# LcsNodes-Extension-GPIO-Board-32-S-B_00_.net
KiCad netlist of a schematic drawn in EasyEDA
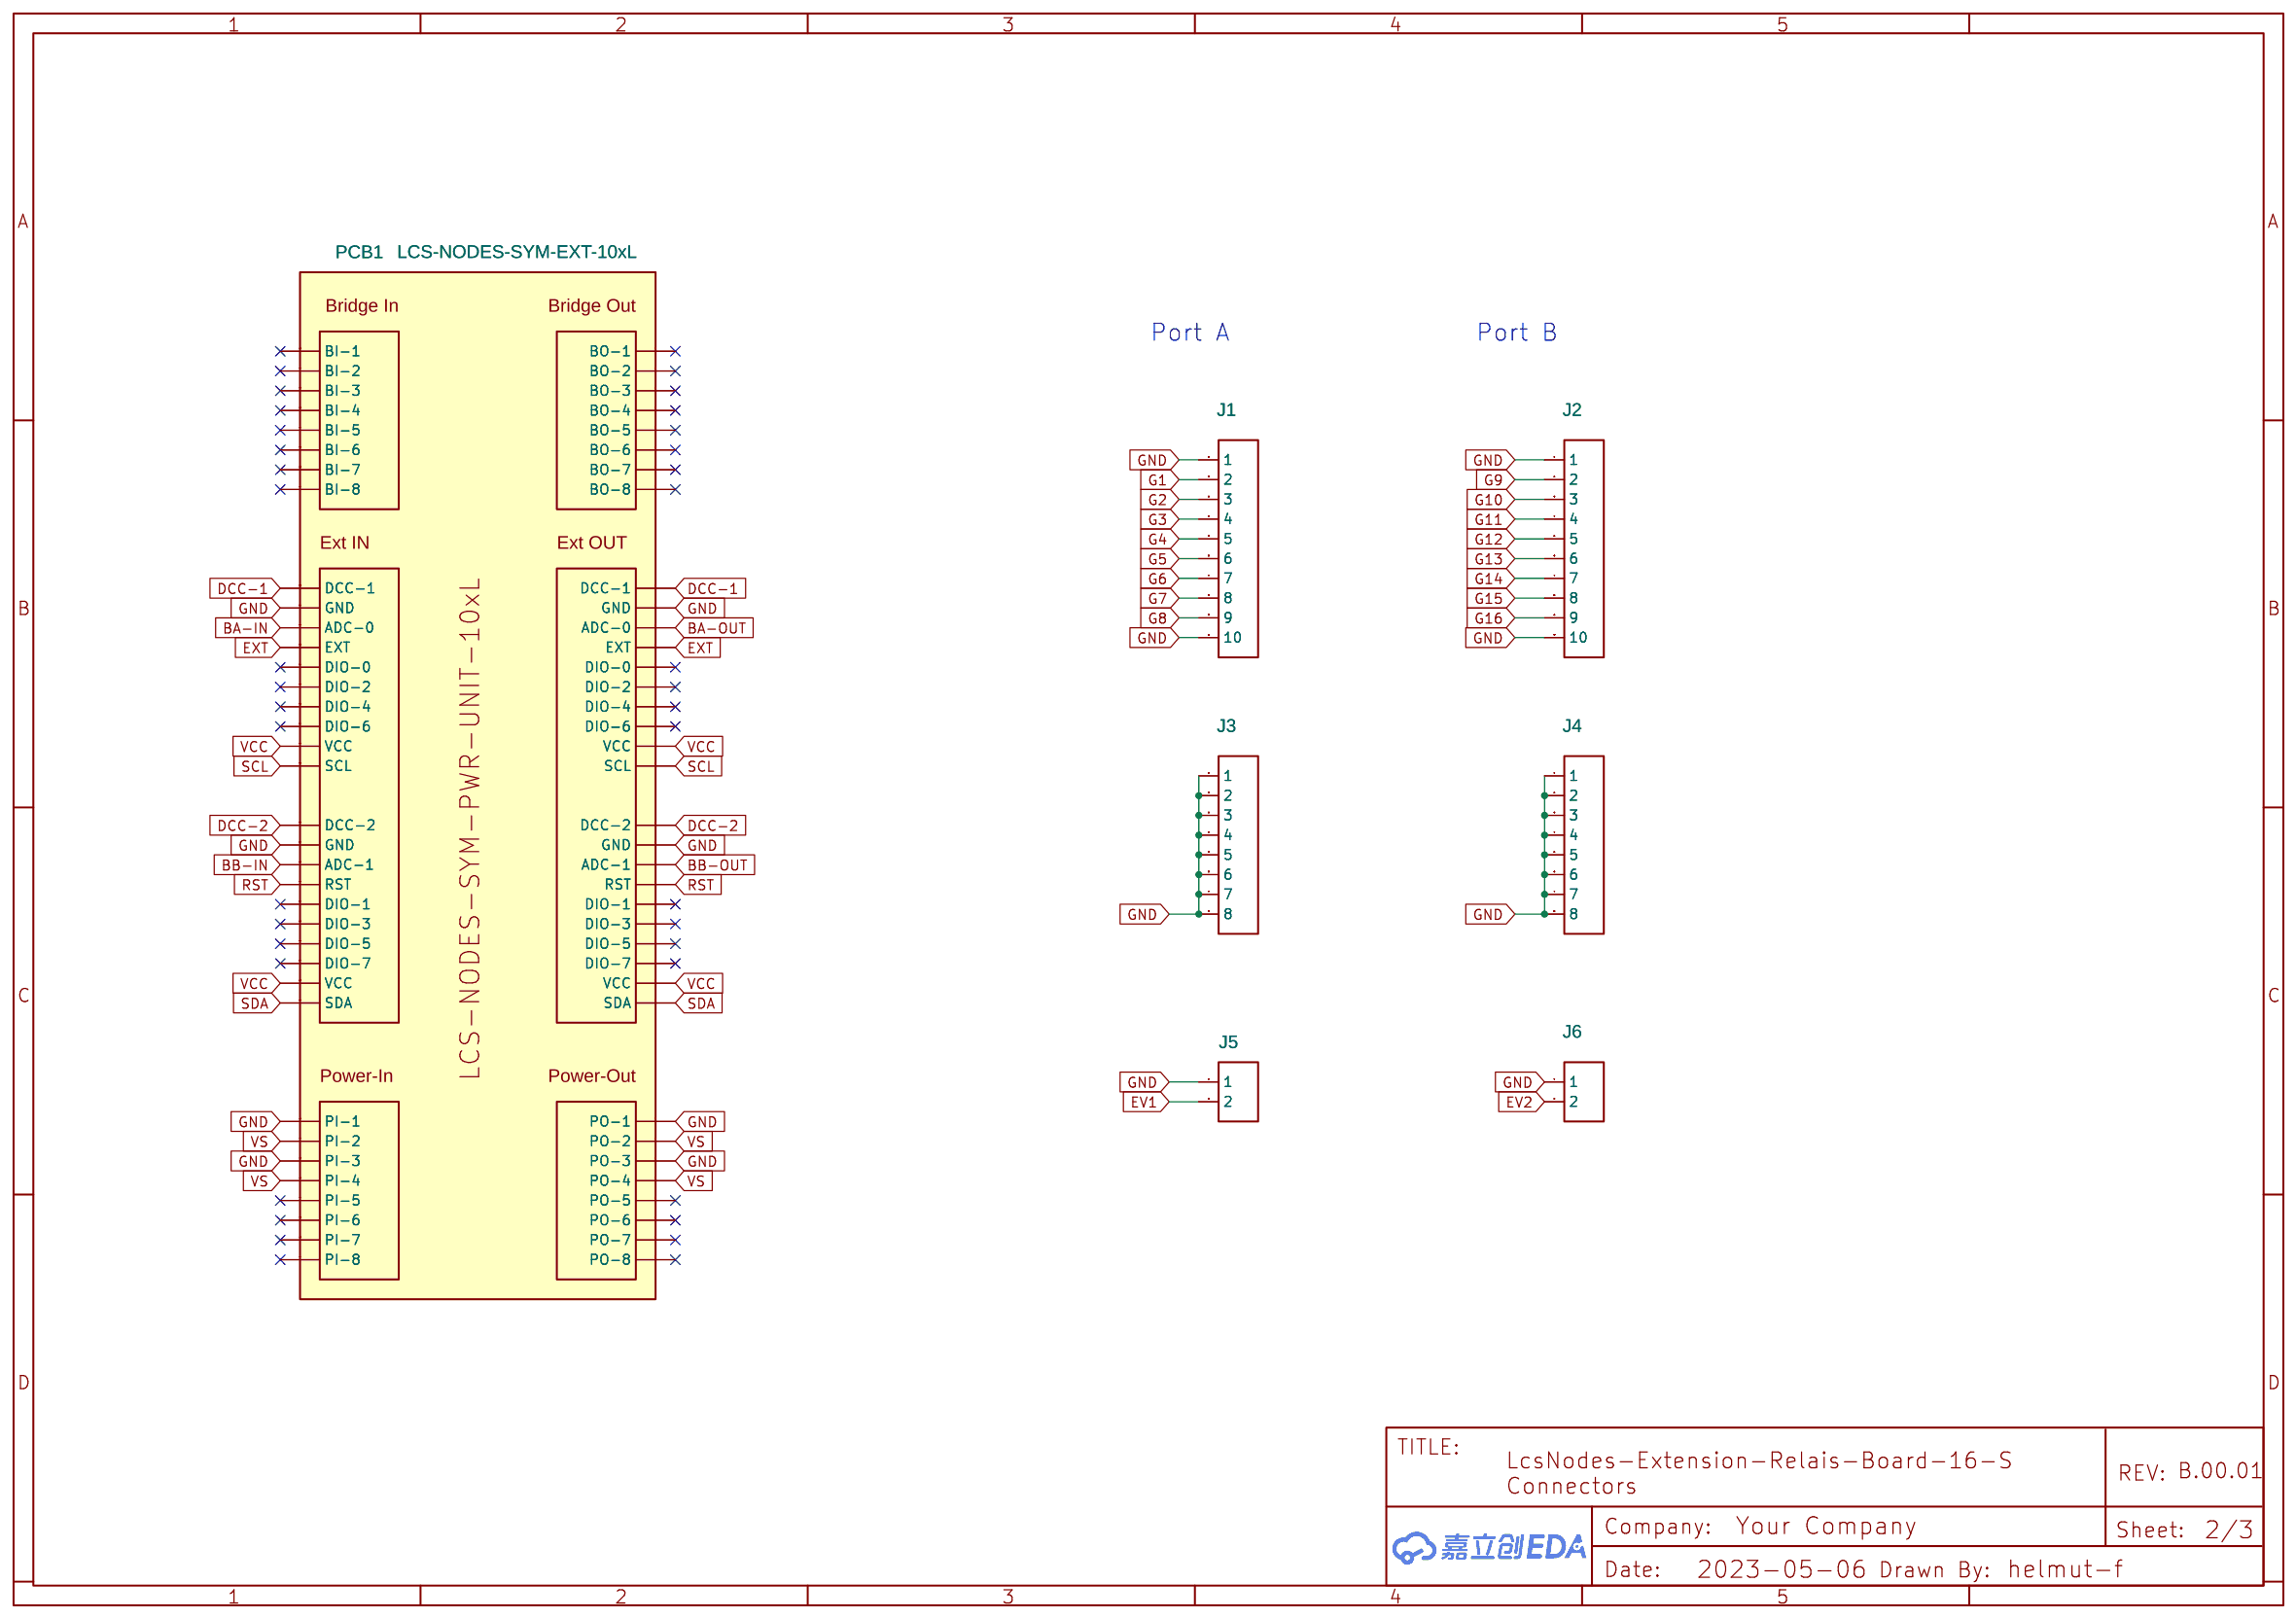
[diagram p0: Connectors]
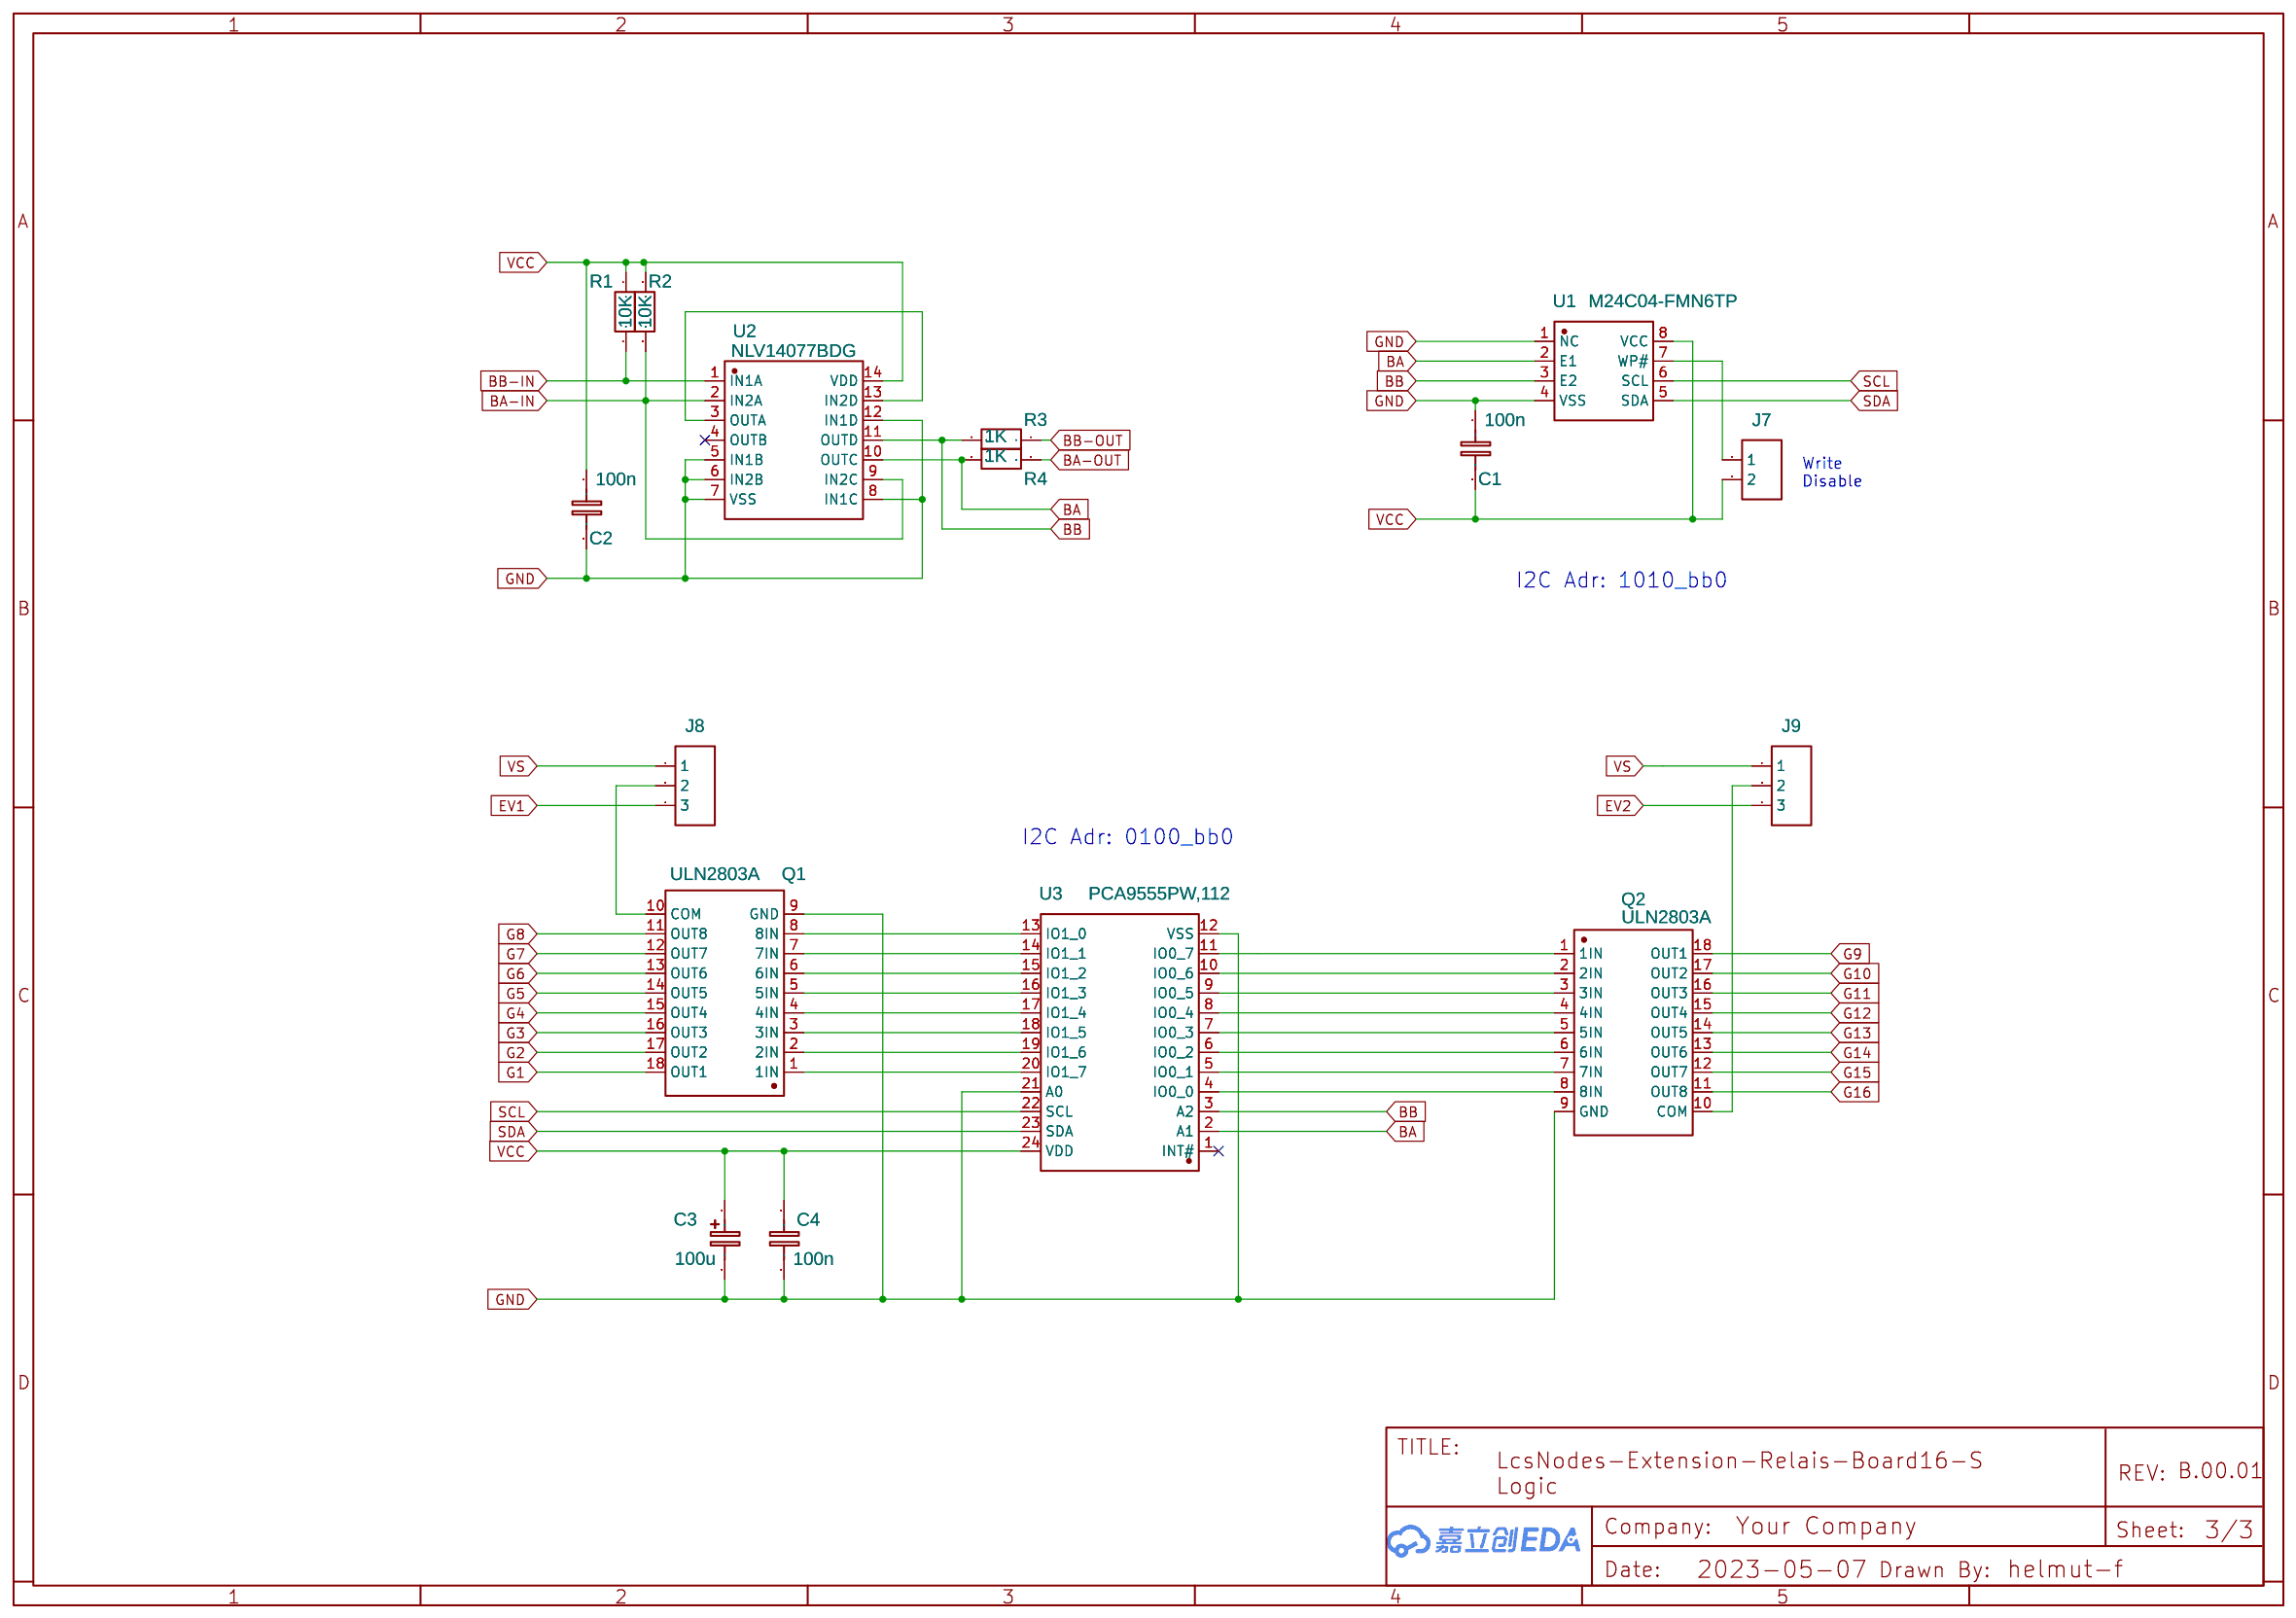
[diagram p1: Logic]
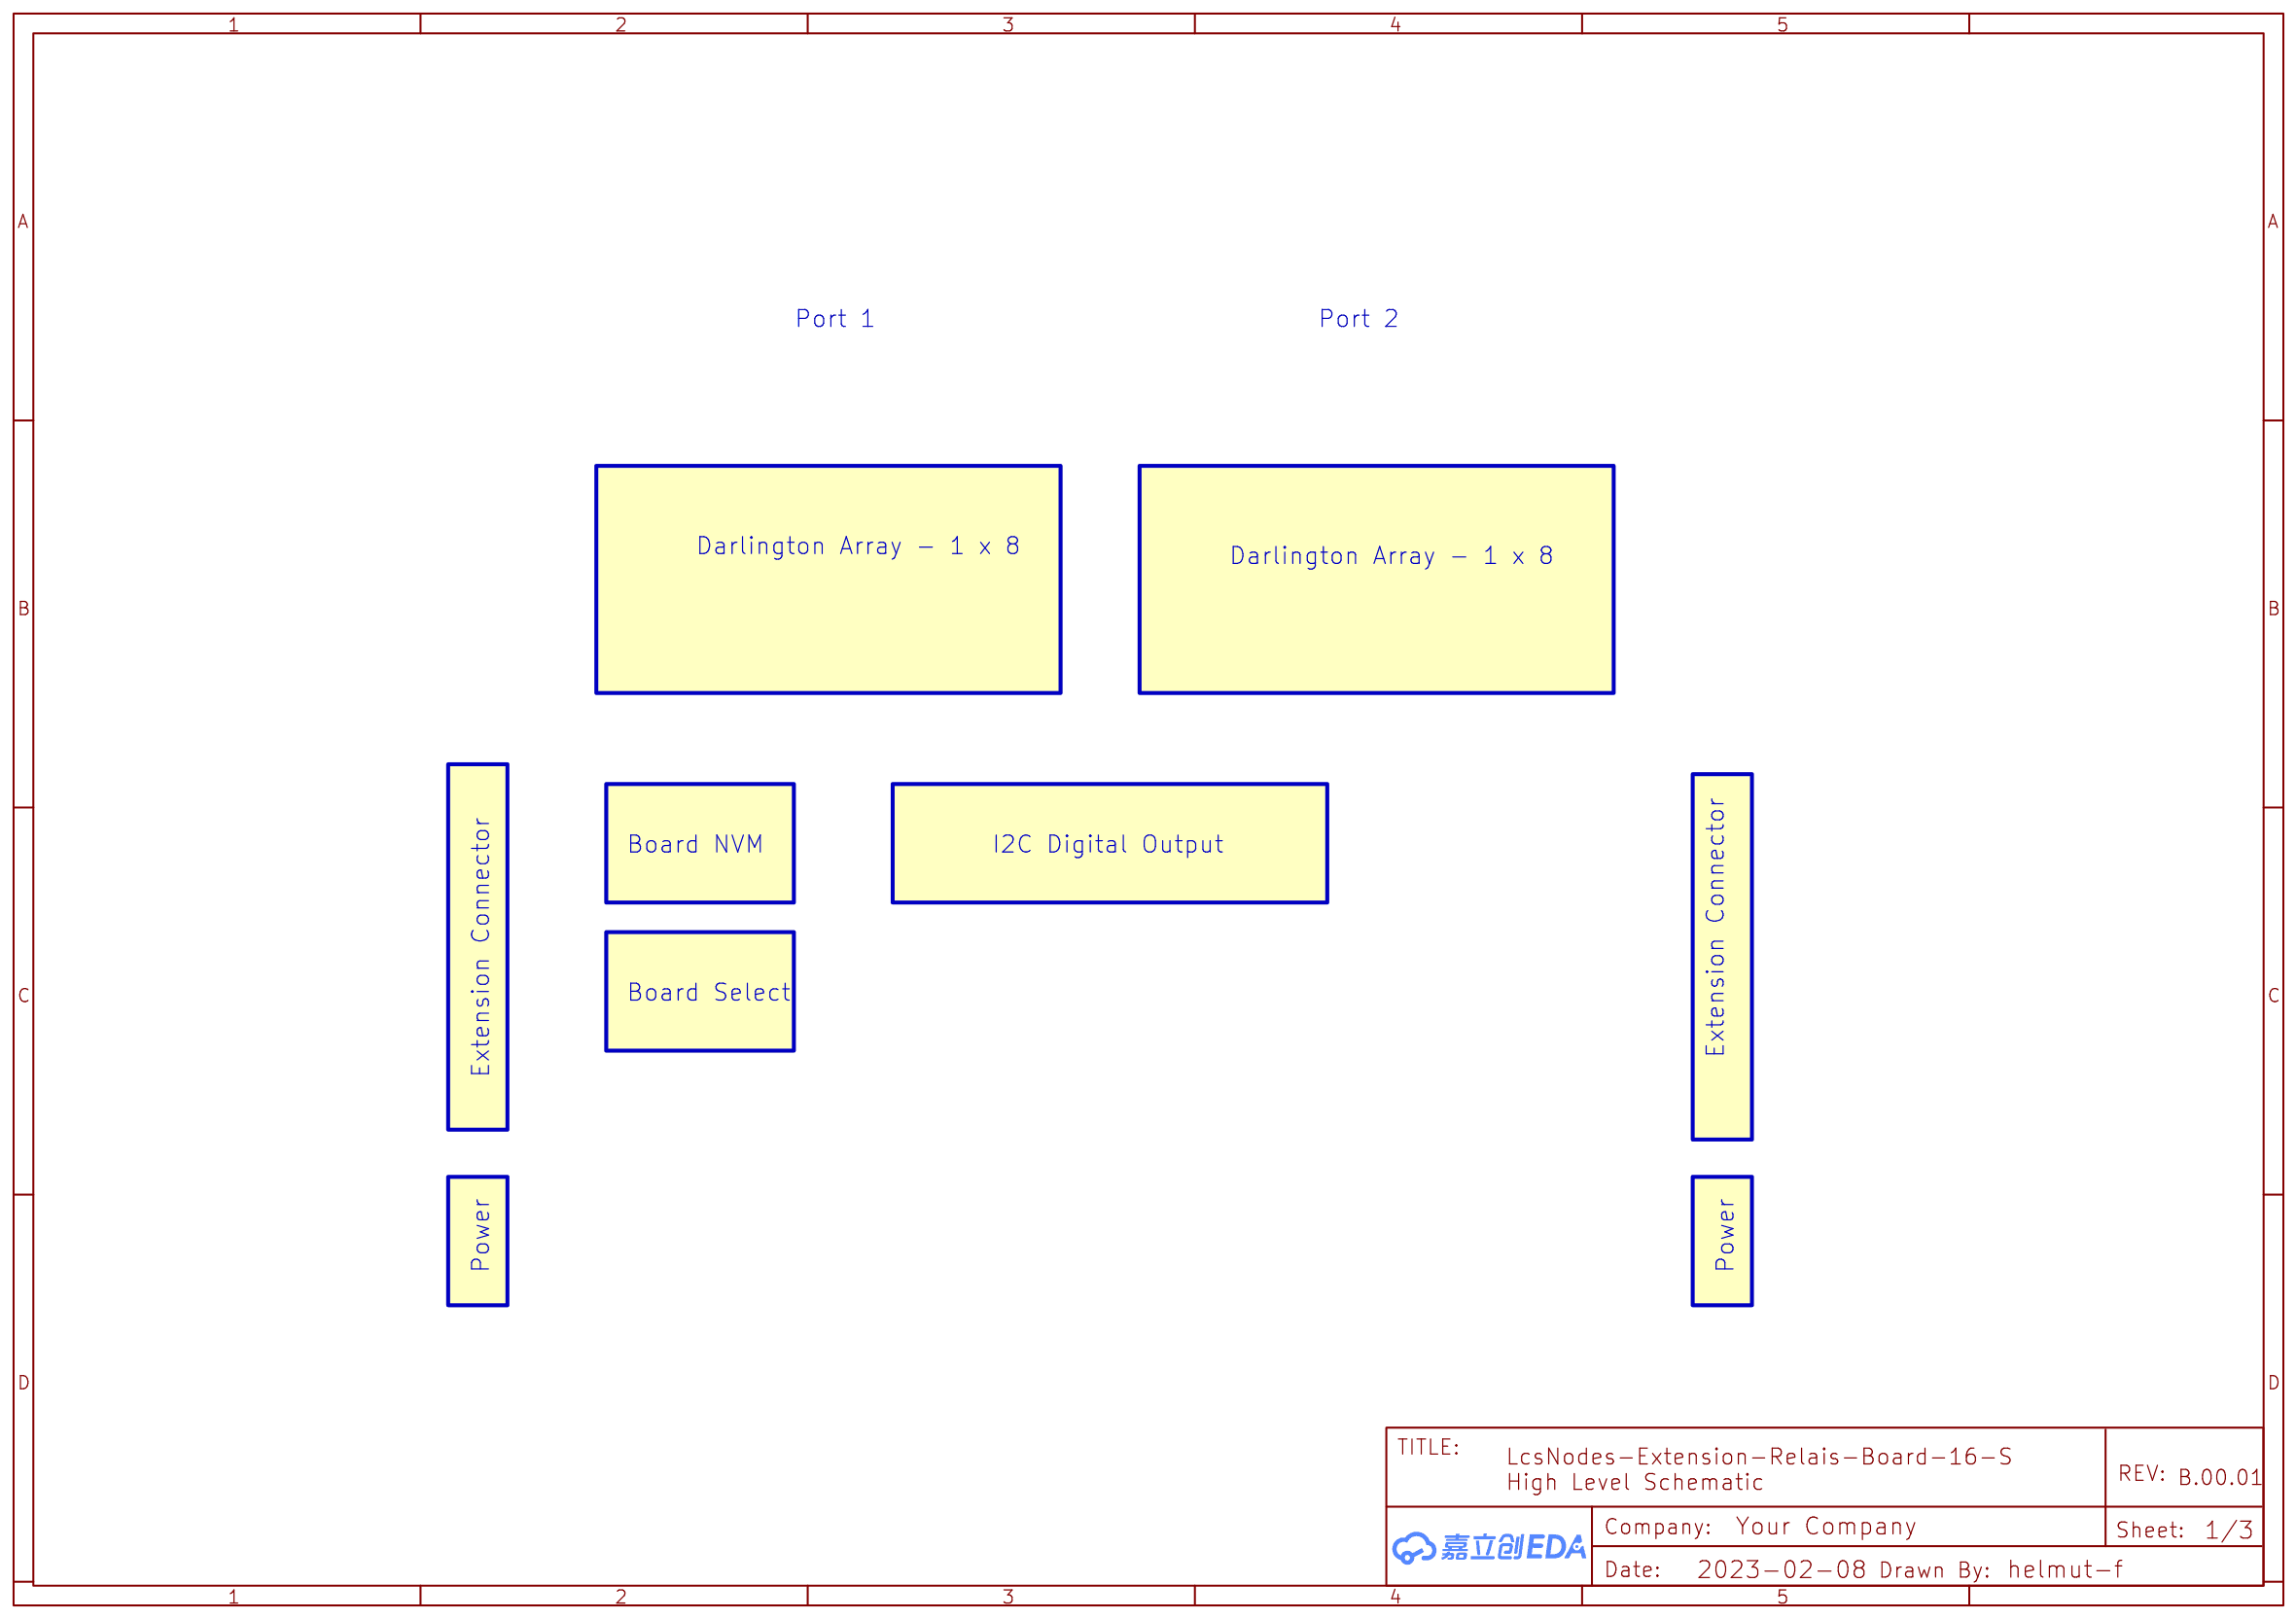
[diagram p2: High Level Schematic]

(export (version "E")
  (design (tool "Eeschema 10.0.6"))
  (components
    (comp (ref "J1") (value "HDR-M-2.54_1x10") (libsource (lib "") (part "HDR-M-2.54_1x10")))
    (comp (ref "J2") (value "HDR-M-2.54_1x10") (libsource (lib "") (part "HDR-M-2.54_1x10")))
    (comp (ref "J3") (value "HDR-M-2.54_1x8") (libsource (lib "") (part "HDR-M-2.54_1x8")))
    (comp (ref "J4") (value "HDR-M-2.54_1x8") (libsource (lib "") (part "HDR-M-2.54_1x8")))
    (comp (ref "J5") (value "HDR-M-2.54_1x2") (libsource (lib "") (part "HDR-M-2.54_1x2")))
    (comp (ref "J6") (value "HDR-M-2.54_1x2") (libsource (lib "") (part "HDR-M-2.54_1x2")))
    (comp (ref "PCB1") (value "LCS-NODES-SYM-EXT-10xL") (libsource (lib "") (part "LCS-NODES-SYM-EXT-10xL")))
    (comp (ref "C1") (value "100n") (libsource (lib "") (part "C_0603_EU_2")))
    (comp (ref "C2") (value "100n") (libsource (lib "") (part "C_0603_EU_1")))
    (comp (ref "C3") (value "100u") (libsource (lib "") (part "CE_TH_D4.0×F1.5_EU")))
    (comp (ref "C4") (value "100n") (libsource (lib "") (part "C_0603_EU")))
    (comp (ref "J7") (value "HDR-M-2.54_1x2") (libsource (lib "") (part "HDR-M-2.54_1x2")))
    (comp (ref "J8") (value "HDR-M-2.54_1x3") (libsource (lib "") (part "HDR-M-2.54_1x3")))
    (comp (ref "J9") (value "HDR-M-2.54_1x3") (libsource (lib "") (part "HDR-M-2.54_1x3")))
    (comp (ref "Q1")
      (value "ULN2803A")
      (fields (field (name "Manufacturer") "STMicroelectronics"))
      (libsource (lib "") (part "ULN2803A_1"))
    )
    (comp (ref "Q2")
      (value "ULN2803A")
      (fields (field (name "Manufacturer") "STMicroelectronics"))
      (libsource (lib "") (part "ULN2803A"))
    )
    (comp (ref "R1") (value "10K") (libsource (lib "") (part "R_AXIAL-0.3_EU_1")))
    (comp (ref "R2") (value "10K") (libsource (lib "") (part "R_AXIAL-0.3_EU_1")))
    (comp (ref "R3") (value "1K") (libsource (lib "") (part "R_AXIAL-0.3_EU")))
    (comp (ref "R4") (value "1K") (libsource (lib "") (part "R_AXIAL-0.3_EU")))
    (comp (ref "U1")
      (value "M24C04-FMN6TP")
      (fields (field (name "Manufacturer") "ST(意法半导体)"))
      (libsource (lib "") (part "M24C04-FMN6TP"))
    )
    (comp (ref "U2")
      (value "NLV14077BDG")
      (fields (field (name "Manufacturer") "onsemi(安森美)"))
      (libsource (lib "") (part "NLV14077BDG"))
    )
    (comp (ref "U3")
      (value "PCA9555PW,112")
      (fields (field (name "Manufacturer") "NXP(恩智浦)"))
      (libsource (lib "") (part "PCA9555PW,112"))
    )
  )
  (nets
    (net (code "1") (name "BA") (class "Default")
      (node (ref "R4") (pin "2") (pinfunction "2_2") (pintype "unspecified"))
      (node (ref "U1") (pin "2") (pinfunction "E1_2") (pintype "unspecified"))
      (node (ref "U2") (pin "10") (pinfunction "OUTC_10") (pintype "unspecified"))
      (node (ref "U3") (pin "2") (pinfunction "A1_2") (pintype "unspecified"))
    )
    (net (code "2") (name "BA-IN") (class "Default")
      (node (ref "PCB1") (pin "22") (pinfunction "ADC-0_22") (pintype "unspecified"))
      (node (ref "R2") (pin "2") (pinfunction "2_2") (pintype "unspecified"))
      (node (ref "U2") (pin "2") (pinfunction "IN2A_2") (pintype "unspecified"))
      (node (ref "U2") (pin "9") (pinfunction "IN2C_9") (pintype "unspecified"))
    )
    (net (code "3") (name "BA-OUT") (class "Default")
      (node (ref "PCB1") (pin "62") (pinfunction "ADC-0_62") (pintype "unspecified"))
      (node (ref "R4") (pin "1") (pinfunction "1_1") (pintype "unspecified"))
    )
    (net (code "4") (name "BB") (class "Default")
      (node (ref "R3") (pin "2") (pinfunction "2_2") (pintype "unspecified"))
      (node (ref "U1") (pin "3") (pinfunction "E2_3") (pintype "unspecified"))
      (node (ref "U2") (pin "11") (pinfunction "OUTD_11") (pintype "unspecified"))
      (node (ref "U3") (pin "3") (pinfunction "A2_3") (pintype "unspecified"))
    )
    (net (code "5") (name "BB-IN") (class "Default")
      (node (ref "PCB1") (pin "32") (pinfunction "ADC-1_32") (pintype "unspecified"))
      (node (ref "R1") (pin "2") (pinfunction "2_2") (pintype "unspecified"))
      (node (ref "U2") (pin "1") (pinfunction "IN1A_1") (pintype "unspecified"))
    )
    (net (code "6") (name "BB-OUT") (class "Default")
      (node (ref "PCB1") (pin "72") (pinfunction "ADC-1_72") (pintype "unspecified"))
      (node (ref "R3") (pin "1") (pinfunction "1_1") (pintype "unspecified"))
    )
    (net (code "7") (name "DCC-1") (class "Default")
      (node (ref "PCB1") (pin "20") (pinfunction "DCC-1_20") (pintype "unspecified"))
      (node (ref "PCB1") (pin "60") (pinfunction "DCC-1_60") (pintype "unspecified"))
    )
    (net (code "8") (name "DCC-2") (class "Default")
      (node (ref "PCB1") (pin "30") (pinfunction "DCC-2_30") (pintype "unspecified"))
      (node (ref "PCB1") (pin "70") (pinfunction "DCC-2_70") (pintype "unspecified"))
    )
    (net (code "9") (name "EV1") (class "Default")
      (node (ref "J5") (pin "2") (pinfunction "2_2") (pintype "unspecified"))
      (node (ref "J8") (pin "3") (pinfunction "3_3") (pintype "input"))
    )
    (net (code "10") (name "EV2") (class "Default")
      (node (ref "J6") (pin "2") (pinfunction "2_2") (pintype "unspecified"))
      (node (ref "J9") (pin "3") (pinfunction "3_3") (pintype "input"))
    )
    (net (code "11") (name "EXT") (class "Default")
      (node (ref "PCB1") (pin "23") (pinfunction "EXT_23") (pintype "unspecified"))
      (node (ref "PCB1") (pin "63") (pinfunction "EXT_63") (pintype "unspecified"))
    )
    (net (code "12") (name "G1") (class "Default")
      (node (ref "J1") (pin "2") (pinfunction "2_2") (pintype "unspecified"))
      (node (ref "Q1") (pin "18") (pinfunction "OUT1_18") (pintype "unspecified"))
    )
    (net (code "13") (name "G2") (class "Default")
      (node (ref "J1") (pin "3") (pinfunction "3_3") (pintype "unspecified"))
      (node (ref "Q1") (pin "17") (pinfunction "OUT2_17") (pintype "unspecified"))
    )
    (net (code "14") (name "G3") (class "Default")
      (node (ref "J1") (pin "4") (pinfunction "4_4") (pintype "unspecified"))
      (node (ref "Q1") (pin "16") (pinfunction "OUT3_16") (pintype "unspecified"))
    )
    (net (code "15") (name "G4") (class "Default")
      (node (ref "J1") (pin "5") (pinfunction "5_5") (pintype "unspecified"))
      (node (ref "Q1") (pin "15") (pinfunction "OUT4_15") (pintype "unspecified"))
    )
    (net (code "16") (name "G5") (class "Default")
      (node (ref "J1") (pin "6") (pinfunction "6_6") (pintype "unspecified"))
      (node (ref "Q1") (pin "14") (pinfunction "OUT5_14") (pintype "unspecified"))
    )
    (net (code "17") (name "G6") (class "Default")
      (node (ref "J1") (pin "7") (pinfunction "7_7") (pintype "unspecified"))
      (node (ref "Q1") (pin "13") (pinfunction "OUT6_13") (pintype "unspecified"))
    )
    (net (code "18") (name "G7") (class "Default")
      (node (ref "J1") (pin "8") (pinfunction "8_8") (pintype "unspecified"))
      (node (ref "Q1") (pin "12") (pinfunction "OUT7_12") (pintype "unspecified"))
    )
    (net (code "19") (name "G8") (class "Default")
      (node (ref "J1") (pin "9") (pinfunction "9_9") (pintype "unspecified"))
      (node (ref "Q1") (pin "11") (pinfunction "OUT8_11") (pintype "unspecified"))
    )
    (net (code "20") (name "G9") (class "Default")
      (node (ref "J2") (pin "2") (pinfunction "2_2") (pintype "unspecified"))
      (node (ref "Q2") (pin "18") (pinfunction "OUT1_18") (pintype "unspecified"))
    )
    (net (code "21") (name "G10") (class "Default")
      (node (ref "J2") (pin "3") (pinfunction "3_3") (pintype "unspecified"))
      (node (ref "Q2") (pin "17") (pinfunction "OUT2_17") (pintype "unspecified"))
    )
    (net (code "22") (name "G11") (class "Default")
      (node (ref "J2") (pin "4") (pinfunction "4_4") (pintype "unspecified"))
      (node (ref "Q2") (pin "16") (pinfunction "OUT3_16") (pintype "unspecified"))
    )
    (net (code "23") (name "G12") (class "Default")
      (node (ref "J2") (pin "5") (pinfunction "5_5") (pintype "unspecified"))
      (node (ref "Q2") (pin "15") (pinfunction "OUT4_15") (pintype "unspecified"))
    )
    (net (code "24") (name "G13") (class "Default")
      (node (ref "J2") (pin "6") (pinfunction "6_6") (pintype "unspecified"))
      (node (ref "Q2") (pin "14") (pinfunction "OUT5_14") (pintype "unspecified"))
    )
    (net (code "25") (name "G14") (class "Default")
      (node (ref "J2") (pin "7") (pinfunction "7_7") (pintype "unspecified"))
      (node (ref "Q2") (pin "13") (pinfunction "OUT6_13") (pintype "unspecified"))
    )
    (net (code "26") (name "G15") (class "Default")
      (node (ref "J2") (pin "8") (pinfunction "8_8") (pintype "unspecified"))
      (node (ref "Q2") (pin "12") (pinfunction "OUT7_12") (pintype "unspecified"))
    )
    (net (code "27") (name "G16") (class "Default")
      (node (ref "J2") (pin "9") (pinfunction "9_9") (pintype "unspecified"))
      (node (ref "Q2") (pin "11") (pinfunction "OUT8_11") (pintype "unspecified"))
    )
    (net (code "28") (name "GND") (class "Default")
      (node (ref "C1") (pin "1") (pinfunction "1_1") (pintype "unspecified"))
      (node (ref "C2") (pin "2") (pinfunction "2_2") (pintype "unspecified"))
      (node (ref "C3") (pin "2") (pinfunction "2_2") (pintype "unspecified"))
      (node (ref "C4") (pin "2") (pinfunction "2_2") (pintype "unspecified"))
      (node (ref "J1") (pin "1") (pinfunction "1_1") (pintype "unspecified"))
      (node (ref "J1") (pin "10") (pinfunction "10_10") (pintype "unspecified"))
      (node (ref "J2") (pin "1") (pinfunction "1_1") (pintype "unspecified"))
      (node (ref "J2") (pin "10") (pinfunction "10_10") (pintype "unspecified"))
      (node (ref "J3") (pin "1") (pinfunction "1_1") (pintype "unspecified"))
      (node (ref "J3") (pin "2") (pinfunction "2_2") (pintype "unspecified"))
      (node (ref "J3") (pin "3") (pinfunction "3_3") (pintype "unspecified"))
      (node (ref "J3") (pin "4") (pinfunction "4_4") (pintype "unspecified"))
      (node (ref "J3") (pin "5") (pinfunction "5_5") (pintype "unspecified"))
      (node (ref "J3") (pin "6") (pinfunction "6_6") (pintype "unspecified"))
      (node (ref "J3") (pin "7") (pinfunction "7_7") (pintype "unspecified"))
      (node (ref "J3") (pin "8") (pinfunction "8_8") (pintype "unspecified"))
      (node (ref "J4") (pin "1") (pinfunction "1_1") (pintype "unspecified"))
      (node (ref "J4") (pin "2") (pinfunction "2_2") (pintype "unspecified"))
      (node (ref "J4") (pin "3") (pinfunction "3_3") (pintype "unspecified"))
      (node (ref "J4") (pin "4") (pinfunction "4_4") (pintype "unspecified"))
      (node (ref "J4") (pin "5") (pinfunction "5_5") (pintype "unspecified"))
      (node (ref "J4") (pin "6") (pinfunction "6_6") (pintype "unspecified"))
      (node (ref "J4") (pin "7") (pinfunction "7_7") (pintype "unspecified"))
      (node (ref "J4") (pin "8") (pinfunction "8_8") (pintype "unspecified"))
      (node (ref "J5") (pin "1") (pinfunction "1_1") (pintype "unspecified"))
      (node (ref "J6") (pin "1") (pinfunction "1_1") (pintype "unspecified"))
      (node (ref "PCB1") (pin "21") (pinfunction "GND_21") (pintype "unspecified"))
      (node (ref "PCB1") (pin "31") (pinfunction "GND_31") (pintype "unspecified"))
      (node (ref "PCB1") (pin "40") (pinfunction "PI-1_40") (pintype "unspecified"))
      (node (ref "PCB1") (pin "42") (pinfunction "PI-3_42") (pintype "unspecified"))
      (node (ref "PCB1") (pin "61") (pinfunction "GND_61") (pintype "unspecified"))
      (node (ref "PCB1") (pin "71") (pinfunction "GND_71") (pintype "unspecified"))
      (node (ref "PCB1") (pin "80") (pinfunction "PO-1_80") (pintype "unspecified"))
      (node (ref "PCB1") (pin "82") (pinfunction "PO-3_82") (pintype "unspecified"))
      (node (ref "Q1") (pin "9") (pinfunction "GND_9") (pintype "unspecified"))
      (node (ref "Q2") (pin "9") (pinfunction "GND_9") (pintype "unspecified"))
      (node (ref "U1") (pin "1") (pinfunction "NC_1") (pintype "unspecified"))
      (node (ref "U1") (pin "4") (pinfunction "VSS_4") (pintype "unspecified"))
      (node (ref "U2") (pin "12") (pinfunction "IN1D_12") (pintype "unspecified"))
      (node (ref "U2") (pin "5") (pinfunction "IN1B_5") (pintype "unspecified"))
      (node (ref "U2") (pin "6") (pinfunction "IN2B_6") (pintype "unspecified"))
      (node (ref "U2") (pin "7") (pinfunction "VSS_7") (pintype "unspecified"))
      (node (ref "U2") (pin "8") (pinfunction "IN1C_8") (pintype "unspecified"))
      (node (ref "U3") (pin "12") (pinfunction "VSS_12") (pintype "unspecified"))
      (node (ref "U3") (pin "21") (pinfunction "A0_21") (pintype "unspecified"))
    )
    (net (code "29") (name "Net-(Q1-1IN)") (class "Default")
      (node (ref "Q1") (pin "1") (pinfunction "1IN_1") (pintype "unspecified"))
      (node (ref "U3") (pin "20") (pinfunction "IO1_7_20") (pintype "unspecified"))
    )
    (net (code "30") (name "Net-(Q1-2IN)") (class "Default")
      (node (ref "Q1") (pin "2") (pinfunction "2IN_2") (pintype "unspecified"))
      (node (ref "U3") (pin "19") (pinfunction "IO1_6_19") (pintype "unspecified"))
    )
    (net (code "31") (name "Net-(Q1-3IN)") (class "Default")
      (node (ref "Q1") (pin "3") (pinfunction "3IN_3") (pintype "unspecified"))
      (node (ref "U3") (pin "18") (pinfunction "IO1_5_18") (pintype "unspecified"))
    )
    (net (code "32") (name "Net-(Q1-4IN)") (class "Default")
      (node (ref "Q1") (pin "4") (pinfunction "4IN_4") (pintype "unspecified"))
      (node (ref "U3") (pin "17") (pinfunction "IO1_4_17") (pintype "unspecified"))
    )
    (net (code "33") (name "Net-(Q1-5IN)") (class "Default")
      (node (ref "Q1") (pin "5") (pinfunction "5IN_5") (pintype "unspecified"))
      (node (ref "U3") (pin "16") (pinfunction "IO1_3_16") (pintype "unspecified"))
    )
    (net (code "34") (name "Net-(Q1-6IN)") (class "Default")
      (node (ref "Q1") (pin "6") (pinfunction "6IN_6") (pintype "unspecified"))
      (node (ref "U3") (pin "15") (pinfunction "IO1_2_15") (pintype "unspecified"))
    )
    (net (code "35") (name "Net-(Q1-7IN)") (class "Default")
      (node (ref "Q1") (pin "7") (pinfunction "7IN_7") (pintype "unspecified"))
      (node (ref "U3") (pin "14") (pinfunction "IO1_1_14") (pintype "unspecified"))
    )
    (net (code "36") (name "Net-(Q1-8IN)") (class "Default")
      (node (ref "Q1") (pin "8") (pinfunction "8IN_8") (pintype "unspecified"))
      (node (ref "U3") (pin "13") (pinfunction "IO1_0_13") (pintype "unspecified"))
    )
    (net (code "37") (name "Net-(Q1-COM)") (class "Default")
      (node (ref "J8") (pin "2") (pinfunction "2_2") (pintype "input"))
      (node (ref "Q1") (pin "10") (pinfunction "COM_10") (pintype "unspecified"))
    )
    (net (code "38") (name "Net-(Q2-1IN)") (class "Default")
      (node (ref "Q2") (pin "1") (pinfunction "1IN_1") (pintype "unspecified"))
      (node (ref "U3") (pin "11") (pinfunction "IO0_7_11") (pintype "unspecified"))
    )
    (net (code "39") (name "Net-(Q2-2IN)") (class "Default")
      (node (ref "Q2") (pin "2") (pinfunction "2IN_2") (pintype "unspecified"))
      (node (ref "U3") (pin "10") (pinfunction "IO0_6_10") (pintype "unspecified"))
    )
    (net (code "40") (name "Net-(Q2-3IN)") (class "Default")
      (node (ref "Q2") (pin "3") (pinfunction "3IN_3") (pintype "unspecified"))
      (node (ref "U3") (pin "9") (pinfunction "IO0_5_9") (pintype "unspecified"))
    )
    (net (code "41") (name "Net-(Q2-4IN)") (class "Default")
      (node (ref "Q2") (pin "4") (pinfunction "4IN_4") (pintype "unspecified"))
      (node (ref "U3") (pin "8") (pinfunction "IO0_4_8") (pintype "unspecified"))
    )
    (net (code "42") (name "Net-(Q2-5IN)") (class "Default")
      (node (ref "Q2") (pin "5") (pinfunction "5IN_5") (pintype "unspecified"))
      (node (ref "U3") (pin "7") (pinfunction "IO0_3_7") (pintype "unspecified"))
    )
    (net (code "43") (name "Net-(Q2-6IN)") (class "Default")
      (node (ref "Q2") (pin "6") (pinfunction "6IN_6") (pintype "unspecified"))
      (node (ref "U3") (pin "6") (pinfunction "IO0_2_6") (pintype "unspecified"))
    )
    (net (code "44") (name "Net-(Q2-7IN)") (class "Default")
      (node (ref "Q2") (pin "7") (pinfunction "7IN_7") (pintype "unspecified"))
      (node (ref "U3") (pin "5") (pinfunction "IO0_1_5") (pintype "unspecified"))
    )
    (net (code "45") (name "Net-(Q2-8IN)") (class "Default")
      (node (ref "Q2") (pin "8") (pinfunction "8IN_8") (pintype "unspecified"))
      (node (ref "U3") (pin "4") (pinfunction "IO0_0_4") (pintype "unspecified"))
    )
    (net (code "46") (name "Net-(Q2-COM)") (class "Default")
      (node (ref "J9") (pin "2") (pinfunction "2_2") (pintype "input"))
      (node (ref "Q2") (pin "10") (pinfunction "COM_10") (pintype "unspecified"))
    )
    (net (code "47") (name "Net-(U1-WP#)") (class "Default")
      (node (ref "J7") (pin "1") (pinfunction "1_1") (pintype "unspecified"))
      (node (ref "U1") (pin "7") (pinfunction "WP#_7") (pintype "unspecified"))
    )
    (net (code "48") (name "Net-(U2-IN2D)") (class "Default")
      (node (ref "U2") (pin "13") (pinfunction "IN2D_13") (pintype "unspecified"))
      (node (ref "U2") (pin "3") (pinfunction "OUTA_3") (pintype "unspecified"))
    )
    (net (code "49") (name "RST") (class "Default")
      (node (ref "PCB1") (pin "33") (pinfunction "RST_33") (pintype "unspecified"))
      (node (ref "PCB1") (pin "73") (pinfunction "RST_73") (pintype "unspecified"))
    )
    (net (code "50") (name "SCL") (class "Default")
      (node (ref "PCB1") (pin "29") (pinfunction "SCL_29") (pintype "unspecified"))
      (node (ref "PCB1") (pin "69") (pinfunction "SCL_69") (pintype "unspecified"))
      (node (ref "U1") (pin "6") (pinfunction "SCL_6") (pintype "unspecified"))
      (node (ref "U3") (pin "22") (pinfunction "SCL_22") (pintype "unspecified"))
    )
    (net (code "51") (name "SDA") (class "Default")
      (node (ref "PCB1") (pin "39") (pinfunction "SDA_39") (pintype "unspecified"))
      (node (ref "PCB1") (pin "79") (pinfunction "SDA_79") (pintype "unspecified"))
      (node (ref "U1") (pin "5") (pinfunction "SDA_5") (pintype "unspecified"))
      (node (ref "U3") (pin "23") (pinfunction "SDA_23") (pintype "unspecified"))
    )
    (net (code "52") (name "VCC") (class "Default")
      (node (ref "C1") (pin "2") (pinfunction "2_2") (pintype "unspecified"))
      (node (ref "C2") (pin "1") (pinfunction "1_1") (pintype "unspecified"))
      (node (ref "C3") (pin "1") (pinfunction "1_1") (pintype "unspecified"))
      (node (ref "C4") (pin "1") (pinfunction "1_1") (pintype "unspecified"))
      (node (ref "J7") (pin "2") (pinfunction "2_2") (pintype "unspecified"))
      (node (ref "PCB1") (pin "28") (pinfunction "VCC_28") (pintype "unspecified"))
      (node (ref "PCB1") (pin "38") (pinfunction "VCC_38") (pintype "unspecified"))
      (node (ref "PCB1") (pin "68") (pinfunction "VCC_68") (pintype "unspecified"))
      (node (ref "PCB1") (pin "78") (pinfunction "VCC_78") (pintype "unspecified"))
      (node (ref "R1") (pin "1") (pinfunction "1_1") (pintype "unspecified"))
      (node (ref "R2") (pin "1") (pinfunction "1_1") (pintype "unspecified"))
      (node (ref "U1") (pin "8") (pinfunction "VCC_8") (pintype "unspecified"))
      (node (ref "U2") (pin "14") (pinfunction "VDD_14") (pintype "unspecified"))
      (node (ref "U3") (pin "24") (pinfunction "VDD_24") (pintype "unspecified"))
    )
    (net (code "53") (name "VS") (class "Default")
      (node (ref "J8") (pin "1") (pinfunction "1_1") (pintype "input"))
      (node (ref "J9") (pin "1") (pinfunction "1_1") (pintype "input"))
      (node (ref "PCB1") (pin "41") (pinfunction "PI-2_41") (pintype "unspecified"))
      (node (ref "PCB1") (pin "43") (pinfunction "PI-4_43") (pintype "unspecified"))
      (node (ref "PCB1") (pin "81") (pinfunction "PO-2_81") (pintype "unspecified"))
      (node (ref "PCB1") (pin "83") (pinfunction "PO-4_83") (pintype "unspecified"))
    )
    (net (code "54") (name "unconnected-(PCB1-BI-1-Pad10)") (class "Default")
      (node (ref "PCB1") (pin "10") (pinfunction "BI-1_10") (pintype "unspecified+no_connect"))
    )
    (net (code "55") (name "unconnected-(PCB1-BI-2-Pad11)") (class "Default")
      (node (ref "PCB1") (pin "11") (pinfunction "BI-2_11") (pintype "unspecified+no_connect"))
    )
    (net (code "56") (name "unconnected-(PCB1-BI-3-Pad12)") (class "Default")
      (node (ref "PCB1") (pin "12") (pinfunction "BI-3_12") (pintype "unspecified+no_connect"))
    )
    (net (code "57") (name "unconnected-(PCB1-BI-4-Pad13)") (class "Default")
      (node (ref "PCB1") (pin "13") (pinfunction "BI-4_13") (pintype "unspecified+no_connect"))
    )
    (net (code "58") (name "unconnected-(PCB1-BI-5-Pad14)") (class "Default")
      (node (ref "PCB1") (pin "14") (pinfunction "BI-5_14") (pintype "unspecified+no_connect"))
    )
    (net (code "59") (name "unconnected-(PCB1-BI-6-Pad15)") (class "Default")
      (node (ref "PCB1") (pin "15") (pinfunction "BI-6_15") (pintype "unspecified+no_connect"))
    )
    (net (code "60") (name "unconnected-(PCB1-BI-7-Pad16)") (class "Default")
      (node (ref "PCB1") (pin "16") (pinfunction "BI-7_16") (pintype "unspecified+no_connect"))
    )
    (net (code "61") (name "unconnected-(PCB1-BI-8-Pad17)") (class "Default")
      (node (ref "PCB1") (pin "17") (pinfunction "BI-8_17") (pintype "unspecified+no_connect"))
    )
    (net (code "62") (name "unconnected-(PCB1-BO-1-Pad50)") (class "Default")
      (node (ref "PCB1") (pin "50") (pinfunction "BO-1_50") (pintype "unspecified+no_connect"))
    )
    (net (code "63") (name "unconnected-(PCB1-BO-2-Pad51)") (class "Default")
      (node (ref "PCB1") (pin "51") (pinfunction "BO-2_51") (pintype "unspecified+no_connect"))
    )
    (net (code "64") (name "unconnected-(PCB1-BO-3-Pad52)") (class "Default")
      (node (ref "PCB1") (pin "52") (pinfunction "BO-3_52") (pintype "unspecified+no_connect"))
    )
    (net (code "65") (name "unconnected-(PCB1-BO-4-Pad53)") (class "Default")
      (node (ref "PCB1") (pin "53") (pinfunction "BO-4_53") (pintype "unspecified+no_connect"))
    )
    (net (code "66") (name "unconnected-(PCB1-BO-5-Pad54)") (class "Default")
      (node (ref "PCB1") (pin "54") (pinfunction "BO-5_54") (pintype "unspecified+no_connect"))
    )
    (net (code "67") (name "unconnected-(PCB1-BO-6-Pad55)") (class "Default")
      (node (ref "PCB1") (pin "55") (pinfunction "BO-6_55") (pintype "unspecified+no_connect"))
    )
    (net (code "68") (name "unconnected-(PCB1-BO-7-Pad56)") (class "Default")
      (node (ref "PCB1") (pin "56") (pinfunction "BO-7_56") (pintype "unspecified+no_connect"))
    )
    (net (code "69") (name "unconnected-(PCB1-BO-8-Pad57)") (class "Default")
      (node (ref "PCB1") (pin "57") (pinfunction "BO-8_57") (pintype "unspecified+no_connect"))
    )
    (net (code "70") (name "unconnected-(PCB1-DIO-0-Pad24)") (class "Default")
      (node (ref "PCB1") (pin "24") (pinfunction "DIO-0_24") (pintype "unspecified+no_connect"))
    )
    (net (code "71") (name "unconnected-(PCB1-DIO-0-Pad64)") (class "Default")
      (node (ref "PCB1") (pin "64") (pinfunction "DIO-0_64") (pintype "unspecified+no_connect"))
    )
    (net (code "72") (name "unconnected-(PCB1-DIO-1-Pad34)") (class "Default")
      (node (ref "PCB1") (pin "34") (pinfunction "DIO-1_34") (pintype "unspecified+no_connect"))
    )
    (net (code "73") (name "unconnected-(PCB1-DIO-1-Pad74)") (class "Default")
      (node (ref "PCB1") (pin "74") (pinfunction "DIO-1_74") (pintype "unspecified+no_connect"))
    )
    (net (code "74") (name "unconnected-(PCB1-DIO-2-Pad25)") (class "Default")
      (node (ref "PCB1") (pin "25") (pinfunction "DIO-2_25") (pintype "unspecified+no_connect"))
    )
    (net (code "75") (name "unconnected-(PCB1-DIO-2-Pad65)") (class "Default")
      (node (ref "PCB1") (pin "65") (pinfunction "DIO-2_65") (pintype "unspecified+no_connect"))
    )
    (net (code "76") (name "unconnected-(PCB1-DIO-3-Pad35)") (class "Default")
      (node (ref "PCB1") (pin "35") (pinfunction "DIO-3_35") (pintype "unspecified+no_connect"))
    )
    (net (code "77") (name "unconnected-(PCB1-DIO-3-Pad75)") (class "Default")
      (node (ref "PCB1") (pin "75") (pinfunction "DIO-3_75") (pintype "unspecified+no_connect"))
    )
    (net (code "78") (name "unconnected-(PCB1-DIO-4-Pad26)") (class "Default")
      (node (ref "PCB1") (pin "26") (pinfunction "DIO-4_26") (pintype "unspecified+no_connect"))
    )
    (net (code "79") (name "unconnected-(PCB1-DIO-4-Pad66)") (class "Default")
      (node (ref "PCB1") (pin "66") (pinfunction "DIO-4_66") (pintype "unspecified+no_connect"))
    )
    (net (code "80") (name "unconnected-(PCB1-DIO-5-Pad36)") (class "Default")
      (node (ref "PCB1") (pin "36") (pinfunction "DIO-5_36") (pintype "unspecified+no_connect"))
    )
    (net (code "81") (name "unconnected-(PCB1-DIO-5-Pad76)") (class "Default")
      (node (ref "PCB1") (pin "76") (pinfunction "DIO-5_76") (pintype "unspecified+no_connect"))
    )
    (net (code "82") (name "unconnected-(PCB1-DIO-6-Pad27)") (class "Default")
      (node (ref "PCB1") (pin "27") (pinfunction "DIO-6_27") (pintype "unspecified+no_connect"))
    )
    (net (code "83") (name "unconnected-(PCB1-DIO-6-Pad67)") (class "Default")
      (node (ref "PCB1") (pin "67") (pinfunction "DIO-6_67") (pintype "unspecified+no_connect"))
    )
    (net (code "84") (name "unconnected-(PCB1-DIO-7-Pad37)") (class "Default")
      (node (ref "PCB1") (pin "37") (pinfunction "DIO-7_37") (pintype "unspecified+no_connect"))
    )
    (net (code "85") (name "unconnected-(PCB1-DIO-7-Pad77)") (class "Default")
      (node (ref "PCB1") (pin "77") (pinfunction "DIO-7_77") (pintype "unspecified+no_connect"))
    )
    (net (code "86") (name "unconnected-(PCB1-PI-5-Pad44)") (class "Default")
      (node (ref "PCB1") (pin "44") (pinfunction "PI-5_44") (pintype "unspecified+no_connect"))
    )
    (net (code "87") (name "unconnected-(PCB1-PI-6-Pad45)") (class "Default")
      (node (ref "PCB1") (pin "45") (pinfunction "PI-6_45") (pintype "unspecified+no_connect"))
    )
    (net (code "88") (name "unconnected-(PCB1-PI-7-Pad46)") (class "Default")
      (node (ref "PCB1") (pin "46") (pinfunction "PI-7_46") (pintype "unspecified+no_connect"))
    )
    (net (code "89") (name "unconnected-(PCB1-PI-8-Pad47)") (class "Default")
      (node (ref "PCB1") (pin "47") (pinfunction "PI-8_47") (pintype "unspecified+no_connect"))
    )
    (net (code "90") (name "unconnected-(PCB1-PO-5-Pad84)") (class "Default")
      (node (ref "PCB1") (pin "84") (pinfunction "PO-5_84") (pintype "unspecified+no_connect"))
    )
    (net (code "91") (name "unconnected-(PCB1-PO-6-Pad85)") (class "Default")
      (node (ref "PCB1") (pin "85") (pinfunction "PO-6_85") (pintype "unspecified+no_connect"))
    )
    (net (code "92") (name "unconnected-(PCB1-PO-7-Pad86)") (class "Default")
      (node (ref "PCB1") (pin "86") (pinfunction "PO-7_86") (pintype "unspecified+no_connect"))
    )
    (net (code "93") (name "unconnected-(PCB1-PO-8-Pad87)") (class "Default")
      (node (ref "PCB1") (pin "87") (pinfunction "PO-8_87") (pintype "unspecified+no_connect"))
    )
    (net (code "94") (name "unconnected-(U2-OUTB-Pad4)") (class "Default")
      (node (ref "U2") (pin "4") (pinfunction "OUTB_4") (pintype "unspecified+no_connect"))
    )
    (net (code "95") (name "unconnected-(U3-INT#-Pad1)") (class "Default")
      (node (ref "U3") (pin "1") (pinfunction "INT#_1") (pintype "unspecified+no_connect"))
    )
  )
)
